# USB_Interface.net
KiCad netlist of a schematic drawn in Altium Designer
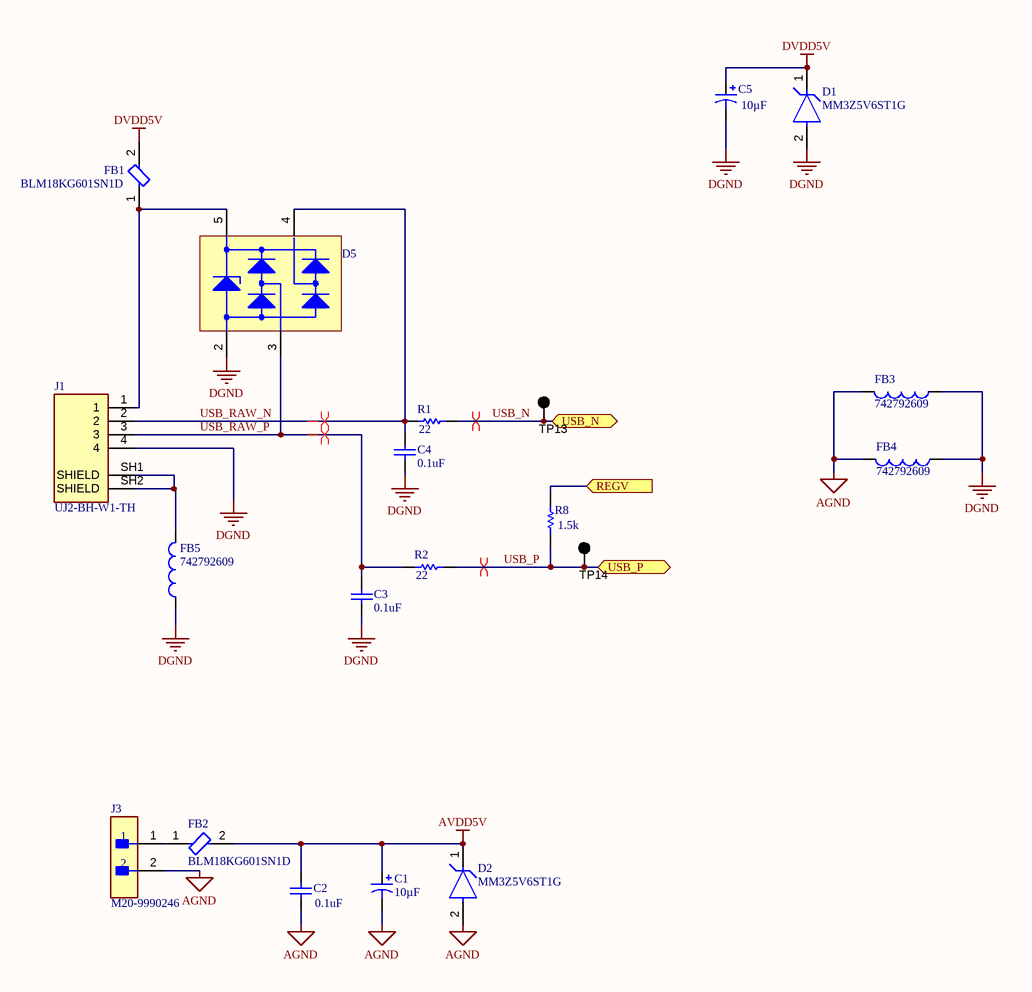
[diagram p0: USB Interface.SchDoc]

(export (version "E")
  (design (tool "Eeschema 10.0.6"))
  (components
    (comp (ref "C1")
      (value "10µF")
      (footprint "1206 TANT CASE A")
      (description "CAP TANT 10UF 16V 20% 1206")
      (fields (field (name "TOLERANCE") "±20%") (field (name "MANUFACTURER") "Kemet"))
      (libsource (lib "SamlibSCH") (part "T491A106M016AT"))
    )
    (comp (ref "C2") (value "0.1uF") (footprint "0603") (libsource (lib "SamlibSCH") (part "C TBD 0603")))
    (comp (ref "C3") (value "0.1uF") (footprint "0603") (libsource (lib "SamlibSCH") (part "C TBD 0603")))
    (comp (ref "C4") (value "0.1uF") (footprint "0603") (libsource (lib "SamlibSCH") (part "C TBD 0603")))
    (comp (ref "C5")
      (value "10µF")
      (footprint "1206 TANT CASE A")
      (description "CAP TANT 10UF 16V 20% 1206")
      (fields (field (name "TOLERANCE") "±20%") (field (name "MANUFACTURER") "Kemet"))
      (libsource (lib "SamlibSCH") (part "T491A106M016AT"))
    )
    (comp (ref "D1")
      (value "MM3Z5V6ST1G")
      (footprint "FP-477-02-MFG")
      (description "DIODE ZENER 5.6V 300MW SOD323")
      (fields (field (name "TOLERANCE") "2%"))
      (libsource (lib "Altium Content Vault") (part "f813f71cba58e380607f5dd3caf9714"))
    )
    (comp (ref "D2")
      (value "MM3Z5V6ST1G")
      (footprint "FP-477-02-MFG")
      (description "DIODE ZENER 5.6V 300MW SOD323")
      (fields (field (name "TOLERANCE") "2%"))
      (libsource (lib "Altium Content Vault") (part "f813f71cba58e380607f5dd3caf9714"))
    )
    (comp (ref "D5")
      (value "5V")
      (footprint "WE-TVS_SOT23-5L")
      (description "WE-TVS TVS Diode – High Speed Series, SOT23-5L, 2+1 Channel, 5V, 2pF")
      (fields
        (field (name "MANUFACTURER PART NUMBER") "824011")
        (field (name "MANUFACTURER") "Wurth Elektronik")
      )
      (libsource (lib "WE-TVS") (part "824011"))
    )
    (comp (ref "FB1")
      (value "BLM18KG601SN1D")
      (footprint "FP-BLM18-0_15-t0_8-IPC_A")
      (description "Chip Ferrite Bead, 0603, 600Ω @ 100MHz, 0.15Ω, 25%, 1.3A")
      (fields (field (name "TOLERANCE") "25%"))
      (libsource (lib "Altium Content Vault") (part "5f30dd21d616792df468990f7003faa"))
    )
    (comp (ref "FB2")
      (value "BLM18KG601SN1D")
      (footprint "FP-BLM18-0_15-t0_8-IPC_A")
      (description "Chip Ferrite Bead, 0603, 600Ω @ 100MHz, 0.15Ω, 25%, 1.3A")
      (fields (field (name "TOLERANCE") "25%"))
      (libsource (lib "Altium Content Vault") (part "5f30dd21d616792df468990f7003faa"))
    )
    (comp (ref "FB3")
      (value "742792609")
      (footprint "WE-CBF_0603_L1.6W0.8H0.8_HC")
      (fields (field (name "TOLERANCE") "25%"))
      (libsource (lib "Altium Content Vault") (part "Ferrite"))
    )
    (comp (ref "FB4")
      (value "742792609")
      (footprint "WE-CBF_0603_L1.6W0.8H0.8_HC")
      (fields (field (name "TOLERANCE") "25%"))
      (libsource (lib "Altium Content Vault") (part "Ferrite"))
    )
    (comp (ref "FB5")
      (value "742792609")
      (footprint "WE-CBF_0603_L1.6W0.8H0.8_HC")
      (fields (field (name "TOLERANCE") "25%"))
      (libsource (lib "Altium Content Vault") (part "Ferrite"))
    )
    (comp (ref "J1")
      (value "UJ2-BH-W1-TH")
      (footprint "CUI_UJ2-BH-W1-TH")
      (description "3 µin Plating Thickness, White Insulator, USB Receptacle")
      (fields (field (name "MF") "{'manufacturer': u'CUI'}"))
      (libsource (lib "Schlib1") (part "UJ2-BH-W1-TH"))
    )
    (comp (ref "J3")
      (value "M20-9990246")
      (footprint "FP-M20-9990246-MFG")
      (description "CONN HEADER VERT 2POS 2.54MM")
      (fields
        (field (name "OCTOPART") "https://octopart.com/m20-9990246-harwin-2590635")
        (field (name "MANUFACTURER") "Harwin")
      )
      (libsource (lib "Altium Content Vault") (part "3bc925449376181038e59eaffc5286c"))
    )
    (comp (ref "R1") (value "22") (footprint "0603") (libsource (lib "SamlibSCH") (part "R TBD 0603")))
    (comp (ref "R2") (value "22") (footprint "0603") (libsource (lib "SamlibSCH") (part "R TBD 0603")))
    (comp (ref "R8") (value "1.5k") (footprint "0603") (libsource (lib "SamlibSCH") (part "R TBD 0603")))
    (comp (ref "TP13")
      (value "5001")
      (footprint "Testpoint pad")
      (description "TEST POINT PC MINI .040\"D BLACK")
      (fields (field (name "MANUFACTURER") "Keystone Electronics"))
      (libsource (lib "SamlibSCH") (part "5001"))
    )
    (comp (ref "TP14")
      (value "5001")
      (footprint "Testpoint pad")
      (description "TEST POINT PC MINI .040\"D BLACK")
      (fields (field (name "MANUFACTURER") "Keystone Electronics"))
      (libsource (lib "SamlibSCH") (part "5001"))
    )
  )
  (nets
    (net (code "1") (name "/REGV") (class "Default")
      (node (ref "R8") (pin "1") (pinfunction "1_1") (pintype "passive"))
    )
    (net (code "2") (name "/USB_N") (class "Default")
      (node (ref "R1") (pin "2") (pinfunction "2_2") (pintype "passive"))
      (node (ref "TP13") (pin "1") (pintype "passive"))
    )
    (net (code "3") (name "/USB_P") (class "Default")
      (node (ref "R2") (pin "2") (pinfunction "2_2") (pintype "passive"))
      (node (ref "R8") (pin "2") (pinfunction "2_2") (pintype "passive"))
      (node (ref "TP14") (pin "1") (pintype "passive"))
    )
    (net (code "4") (name "/USB_RAW_N") (class "Default")
      (node (ref "C4") (pin "2") (pinfunction "2_2") (pintype "passive"))
      (node (ref "D5") (pin "4") (pinfunction "I/O_2_4") (pintype "passive"))
      (node (ref "J1") (pin "2") (pinfunction "2_2") (pintype "passive"))
      (node (ref "R1") (pin "1") (pinfunction "1_1") (pintype "passive"))
    )
    (net (code "5") (name "/USB_RAW_P") (class "Default")
      (node (ref "C3") (pin "2") (pinfunction "2_2") (pintype "passive"))
      (node (ref "D5") (pin "3") (pinfunction "I/O_1_3") (pintype "passive"))
      (node (ref "J1") (pin "3") (pinfunction "3_3") (pintype "passive"))
      (node (ref "R2") (pin "1") (pinfunction "1_1") (pintype "passive"))
    )
    (net (code "6") (name "AGND") (class "Default")
      (node (ref "C1") (pin "1") (pinfunction "1_1") (pintype "passive"))
      (node (ref "C2") (pin "1") (pinfunction "1_1") (pintype "passive"))
      (node (ref "D2") (pin "2") (pinfunction "A_2") (pintype "passive"))
      (node (ref "FB3") (pin "2") (pinfunction "2_2") (pintype "passive"))
      (node (ref "FB4") (pin "2") (pinfunction "2_2") (pintype "passive"))
      (node (ref "J3") (pin "2") (pinfunction "2_2") (pintype "passive"))
    )
    (net (code "7") (name "AVDD5V") (class "Default")
      (node (ref "C1") (pin "2") (pinfunction "2_2") (pintype "passive"))
      (node (ref "C2") (pin "2") (pinfunction "2_2") (pintype "passive"))
      (node (ref "D2") (pin "1") (pinfunction "C_1") (pintype "passive"))
      (node (ref "FB2") (pin "2") (pinfunction "2_2") (pintype "passive"))
    )
    (net (code "8") (name "DGND") (class "Default")
      (node (ref "C3") (pin "1") (pinfunction "1_1") (pintype "passive"))
      (node (ref "C4") (pin "1") (pinfunction "1_1") (pintype "passive"))
      (node (ref "C5") (pin "1") (pinfunction "1_1") (pintype "passive"))
      (node (ref "D1") (pin "2") (pinfunction "A_2") (pintype "passive"))
      (node (ref "D5") (pin "2") (pinfunction "GND_2") (pintype "passive"))
      (node (ref "FB3") (pin "1") (pinfunction "1_1") (pintype "passive"))
      (node (ref "FB4") (pin "1") (pinfunction "1_1") (pintype "passive"))
      (node (ref "FB5") (pin "1") (pinfunction "1_1") (pintype "passive"))
      (node (ref "J1") (pin "4") (pinfunction "4_4") (pintype "passive"))
    )
    (net (code "9") (name "DVDD5V") (class "Default")
      (node (ref "C5") (pin "2") (pinfunction "2_2") (pintype "passive"))
      (node (ref "D1") (pin "1") (pinfunction "C_1") (pintype "passive"))
      (node (ref "FB1") (pin "2") (pinfunction "2_2") (pintype "passive"))
    )
    (net (code "10") (name "Net-(D5-VDD)") (class "Default")
      (node (ref "D5") (pin "5") (pinfunction "VDD_5") (pintype "passive"))
      (node (ref "FB1") (pin "1") (pinfunction "1_1") (pintype "passive"))
      (node (ref "J1") (pin "1") (pinfunction "1_1") (pintype "passive"))
    )
    (net (code "11") (name "Net-(FB2-Pad1)") (class "Default")
      (node (ref "FB2") (pin "1") (pinfunction "1_1") (pintype "passive"))
      (node (ref "J3") (pin "1") (pinfunction "1_1") (pintype "passive"))
    )
    (net (code "12") (name "Net-(FB5-Pad2)") (class "Default")
      (node (ref "FB5") (pin "2") (pinfunction "2_2") (pintype "passive"))
      (node (ref "J1") (pin "SH1") (pinfunction "SHIELD_SH1") (pintype "passive"))
      (node (ref "J1") (pin "SH2") (pinfunction "SHIELD_SH2") (pintype "passive"))
    )
  )
)
